# Power.net
KiCad netlist of a schematic drawn in Altium Designer
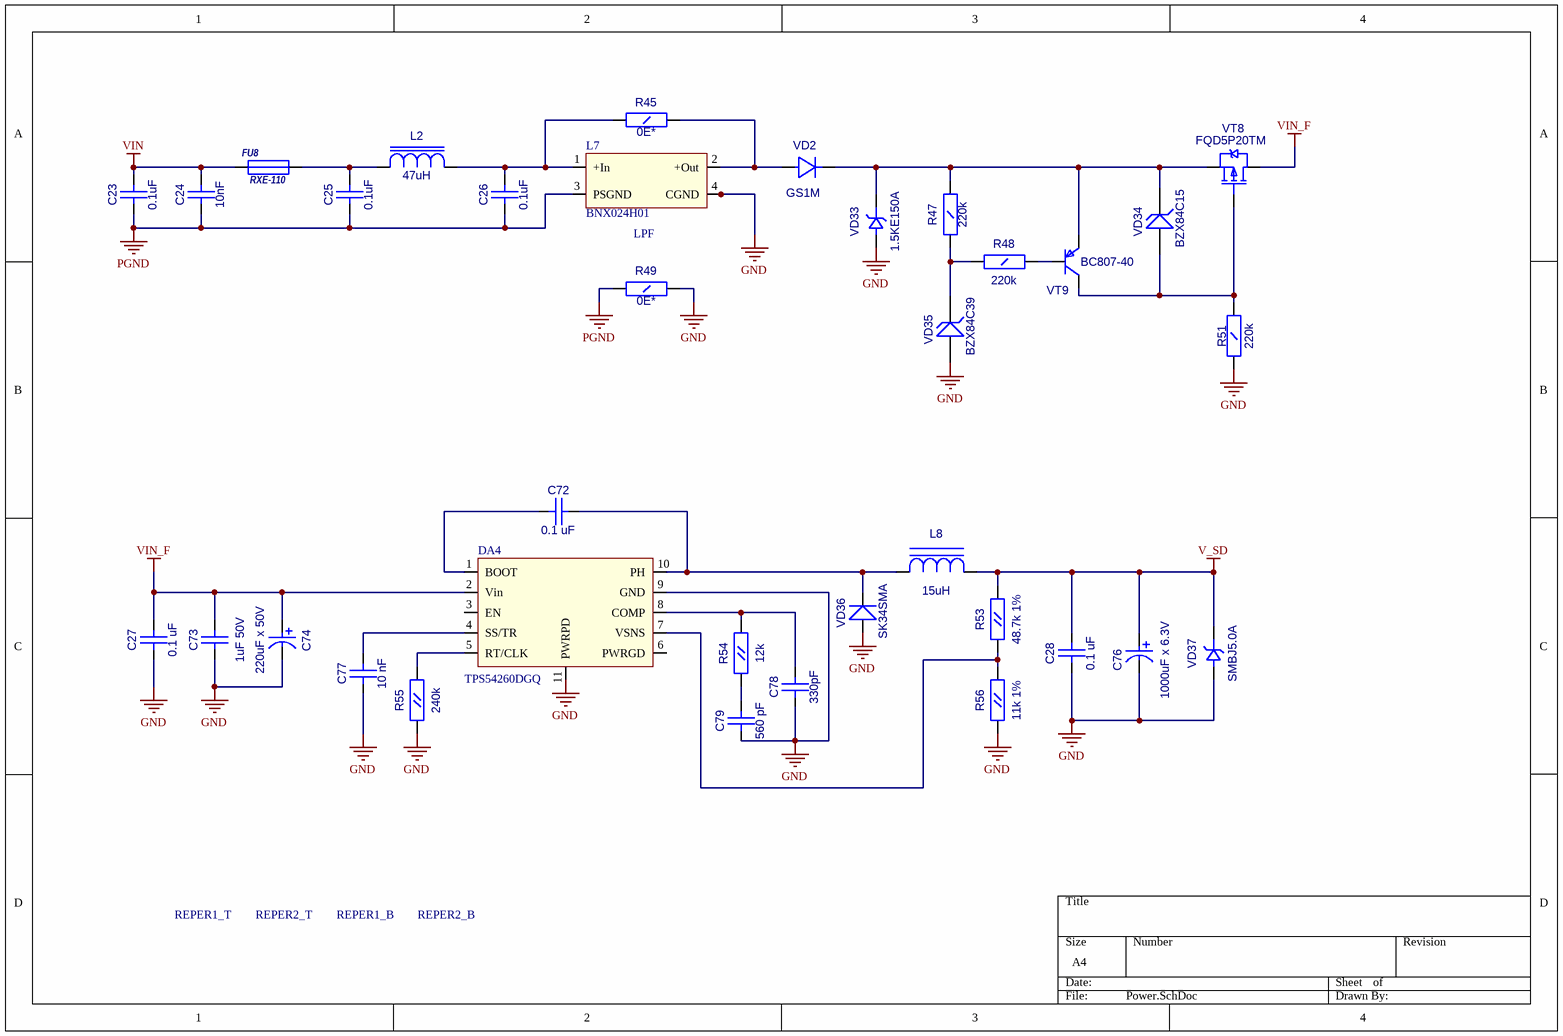
[diagram p0: Power.SchDoc]

(export (version "E")
  (design (tool "Eeschema 10.0.6"))
  (components
    (comp (ref "C23")
      (value "0.1uF")
      (footprint "CC1206")
      (description "CC1206")
      (libsource (lib "gprs_modem_2") (part "CC1206"))
    )
    (comp (ref "C24")
      (value "10nF")
      (footprint "CC1206")
      (description "CC1206")
      (libsource (lib "gprs_modem_2") (part "CC1206"))
    )
    (comp (ref "C25")
      (value "0.1uF")
      (footprint "CC1206")
      (description "CC1206")
      (libsource (lib "gprs_modem_2") (part "CC1206"))
    )
    (comp (ref "C26")
      (value "0.1uF")
      (footprint "CC1206")
      (description "CC1206")
      (libsource (lib "gprs_modem_2") (part "CC1206"))
    )
    (comp (ref "C27")
      (value "0.1 uF")
      (footprint "CC0603")
      (description "CC0603")
      (libsource (lib "gprs_modem_2") (part "CC0603"))
    )
    (comp (ref "C28")
      (value "0.1 uF")
      (footprint "CC0603")
      (description "CC0603")
      (libsource (lib "*") (part "CC0603"))
    )
    (comp (ref "C72")
      (value "0.1 uF")
      (footprint "CC0603")
      (description "CC0603")
      (libsource (lib "gprs_modem_2") (part "CC0603"))
    )
    (comp (ref "C73")
      (value "1uF 50V")
      (footprint "CC1206")
      (description "CC1206")
      (libsource (lib "gprs_modem_2") (part "CC1206"))
    )
    (comp (ref "C74")
      (value "220uF x 50V")
      (footprint "CC16X10_CAP0.5(1)(Primary)")
      (description "CAP0.5(1)")
      (libsource (lib "gprs_modem") (part "CAP0.5(1)"))
    )
    (comp (ref "C76")
      (value "1000uF x 6.3V")
      (footprint "CC16X10_CAP0.5(1)(Primary)")
      (description "CAP0.5(1)")
      (libsource (lib "gprs_modem") (part "CAP0.5(1)"))
    )
    (comp (ref "C77")
      (value "10 nF")
      (footprint "CC0603")
      (description "CC0603")
      (libsource (lib "gprs_modem_2") (part "CC0603"))
    )
    (comp (ref "C78")
      (value "330pF")
      (footprint "CC0603")
      (description "CC0603")
      (libsource (lib "gprs_modem_2") (part "CC0603"))
    )
    (comp (ref "C79")
      (value "560 pF")
      (footprint "CC0603")
      (description "CC0603")
      (libsource (lib "gprs_modem_2") (part "CC0603"))
    )
    (comp (ref "DA4")
      (value "TPS54260DGQ")
      (footprint "S-PDSO-G10")
      (libsource (lib "gprs_modem") (part "TPS54260DGQ"))
    )
    (comp (ref "FU8") (value "RXE-110") (footprint "RXE-110") (libsource (lib "gprs_modem") (part "RXE-110")))
    (comp (ref "L2")
      (value "47uH")
      (footprint "SDR0603")
      (description "SDR0603")
      (libsource (lib "gprs_modem_2") (part "SDR0603"))
    )
    (comp (ref "L7")
      (value "BNX024H01")
      (footprint "BNX024")
      (description "LC Filter")
      (libsource (lib "gprs_modem") (part "BNX024H01"))
    )
    (comp (ref "L8")
      (value "15uH")
      (footprint "SDR0805")
      (description "SDR0805")
      (libsource (lib "gprs_modem") (part "SDR0805"))
    )
    (comp (ref "R45")
      (value "0E*")
      (footprint "RC1206")
      (description "RC1206")
      (libsource (lib "gprs_modem_2") (part "RC1206"))
    )
    (comp (ref "R47")
      (value "220k")
      (footprint "RC1206")
      (description "RC1206")
      (libsource (lib "gprs_modem_2") (part "RC1206"))
    )
    (comp (ref "R48")
      (value "220k")
      (footprint "RC1206")
      (description "RC1206")
      (libsource (lib "gprs_modem_2") (part "RC1206"))
    )
    (comp (ref "R49")
      (value "0E*")
      (footprint "RC1206")
      (description "RC1206")
      (libsource (lib "gprs_modem_2") (part "RC1206"))
    )
    (comp (ref "R51")
      (value "220k")
      (footprint "RC1206")
      (description "RC1206")
      (libsource (lib "gprs_modem_2") (part "RC1206"))
    )
    (comp (ref "R53")
      (value "48.7k 1%")
      (footprint "RC0603")
      (description "RC0603")
      (libsource (lib "gprs_modem_2") (part "RC0603"))
    )
    (comp (ref "R54")
      (value "12k")
      (footprint "RC0603")
      (description "RC0603")
      (libsource (lib "gprs_modem_2") (part "RC0603"))
    )
    (comp (ref "R55")
      (value "240k")
      (footprint "RC0603")
      (description "RC0603")
      (libsource (lib "gprs_modem_2") (part "RC0603"))
    )
    (comp (ref "R56")
      (value "11k 1%")
      (footprint "RC0603")
      (description "RC0603")
      (libsource (lib "gprs_modem_2") (part "RC0603"))
    )
    (comp (ref "REPER1_B")
      (value "REPER1.2")
      (footprint "REPER1.2")
      (libsource (lib "gprs_modem") (part "REPER1.2"))
    )
    (comp (ref "REPER1_T")
      (value "REPER1.2")
      (footprint "REPER1.2")
      (libsource (lib "gprs_modem") (part "REPER1.2"))
    )
    (comp (ref "REPER2_B")
      (value "REPER1.2")
      (footprint "REPER1.2")
      (libsource (lib "gprs_modem") (part "REPER1.2"))
    )
    (comp (ref "REPER2_T")
      (value "REPER1.2")
      (footprint "REPER1.2")
      (libsource (lib "gprs_modem") (part "REPER1.2"))
    )
    (comp (ref "VD2") (value "GS1M") (footprint "SMA") (libsource (lib "gprs_modem") (part "GS1M")))
    (comp (ref "VD33")
      (value "1.5KE150A")
      (footprint "DO-201")
      (description "1.5KE")
      (libsource (lib "gprs_modem") (part "1.5KE"))
    )
    (comp (ref "VD34")
      (value "BZX84C15")
      (footprint "SOT-23(123)")
      (description "Zener Voltage Regulator Diode")
      (libsource (lib "gprs_modem_2") (part "BZX84"))
    )
    (comp (ref "VD35")
      (value "BZX84C39")
      (footprint "SOT-23(123)")
      (description "Zener Voltage Regulator Diode")
      (libsource (lib "gprs_modem_2") (part "BZX84"))
    )
    (comp (ref "VD36")
      (value "SK34SMA")
      (footprint "SMA")
      (description "Schottky Rectifier")
      (libsource (lib "gprs_modem") (part "SK34SMA"))
    )
    (comp (ref "VD37")
      (value "SMBJ5.0A")
      (footprint "SMB")
      (description "SMBJ")
      (libsource (lib "gprs_modem") (part "SMBJ"))
    )
    (comp (ref "VT8")
      (value "FQD5P20TM")
      (footprint "D-PAK(TO-252AA)")
      (description "HEXFET Power MOSFET")
      (libsource (lib "gprs_modem") (part "IRFR9220"))
    )
    (comp (ref "VT9")
      (value "BC807-40")
      (footprint "SOT-23(123)")
      (description "BC857B")
      (libsource (lib "gprs_modem") (part "BC857B"))
    )
  )
  (nets
    (net (code "1") (name "GND") (class "Default")
      (node (ref "C27") (pin "1") (pinfunction "A_1") (pintype "passive"))
      (node (ref "C28") (pin "2") (pinfunction "B_2") (pintype "passive"))
      (node (ref "C73") (pin "1") (pinfunction "A_1") (pintype "passive"))
      (node (ref "C74") (pin "1") (pintype "passive"))
      (node (ref "C76") (pin "1") (pintype "passive"))
      (node (ref "C77") (pin "1") (pinfunction "A_1") (pintype "passive"))
      (node (ref "C78") (pin "1") (pinfunction "A_1") (pintype "passive"))
      (node (ref "C79") (pin "1") (pinfunction "A_1") (pintype "passive"))
      (node (ref "DA4") (pin "11") (pinfunction "PWRPD_11") (pintype "passive"))
      (node (ref "DA4") (pin "9") (pinfunction "GND_9") (pintype "passive"))
      (node (ref "L7") (pin "4") (pinfunction "CGND_4") (pintype "passive"))
      (node (ref "L7") (pin "5") (pinfunction "5_5") (pintype "passive"))
      (node (ref "L7") (pin "6") (pinfunction "6_6") (pintype "passive"))
      (node (ref "R49") (pin "2") (pinfunction "B_2") (pintype "passive"))
      (node (ref "R51") (pin "2") (pinfunction "B_2") (pintype "passive"))
      (node (ref "R55") (pin "1") (pinfunction "A_1") (pintype "passive"))
      (node (ref "R56") (pin "1") (pinfunction "A_1") (pintype "passive"))
      (node (ref "VD33") (pin "1") (pinfunction "A_1") (pintype "passive"))
      (node (ref "VD35") (pin "1") (pinfunction "A_1") (pintype "passive"))
      (node (ref "VD36") (pin "1") (pinfunction "A_1") (pintype "passive"))
      (node (ref "VD37") (pin "1") (pinfunction "A_1") (pintype "passive"))
    )
    (net (code "2") (name "Net-(C25-B)") (class "Default")
      (node (ref "C25") (pin "2") (pinfunction "B_2") (pintype "passive"))
      (node (ref "FU8") (pin "2") (pintype "passive"))
      (node (ref "L2") (pin "1") (pintype "passive"))
    )
    (net (code "3") (name "Net-(C26-B)") (class "Default")
      (node (ref "C26") (pin "2") (pinfunction "B_2") (pintype "passive"))
      (node (ref "L2") (pin "2") (pintype "passive"))
      (node (ref "L7") (pin "1") (pinfunction "+In_1") (pintype "passive"))
      (node (ref "R45") (pin "1") (pinfunction "A_1") (pintype "passive"))
    )
    (net (code "4") (name "Net-(C72-A)") (class "Default")
      (node (ref "C72") (pin "1") (pinfunction "A_1") (pintype "passive"))
      (node (ref "DA4") (pin "1") (pinfunction "BOOT_1") (pintype "passive"))
    )
    (net (code "5") (name "Net-(C72-B)") (class "Default")
      (node (ref "C72") (pin "2") (pinfunction "B_2") (pintype "passive"))
      (node (ref "DA4") (pin "10") (pinfunction "PH_10") (pintype "passive"))
      (node (ref "L8") (pin "1") (pinfunction "C_1") (pintype "passive"))
      (node (ref "VD36") (pin "2") (pinfunction "K_2") (pintype "passive"))
    )
    (net (code "6") (name "Net-(C77-B)") (class "Default")
      (node (ref "C77") (pin "2") (pinfunction "B_2") (pintype "passive"))
      (node (ref "DA4") (pin "4") (pinfunction "SS/TR_4") (pintype "passive"))
    )
    (net (code "7") (name "Net-(C78-B)") (class "Default")
      (node (ref "C78") (pin "2") (pinfunction "B_2") (pintype "passive"))
      (node (ref "DA4") (pin "8") (pinfunction "COMP_8") (pintype "passive"))
      (node (ref "R54") (pin "2") (pinfunction "B_2") (pintype "passive"))
    )
    (net (code "8") (name "Net-(C79-B)") (class "Default")
      (node (ref "C79") (pin "2") (pinfunction "B_2") (pintype "passive"))
      (node (ref "R54") (pin "1") (pinfunction "A_1") (pintype "passive"))
    )
    (net (code "9") (name "Net-(DA4-RT{slash}CLK)") (class "Default")
      (node (ref "DA4") (pin "5") (pinfunction "RT/CLK_5") (pintype "passive"))
      (node (ref "R55") (pin "2") (pinfunction "B_2") (pintype "passive"))
    )
    (net (code "10") (name "Net-(DA4-VSNS)") (class "Default")
      (node (ref "DA4") (pin "7") (pinfunction "VSNS_7") (pintype "passive"))
      (node (ref "R53") (pin "1") (pinfunction "A_1") (pintype "passive"))
      (node (ref "R56") (pin "2") (pinfunction "B_2") (pintype "passive"))
    )
    (net (code "11") (name "Net-(L7-+Out)") (class "Default")
      (node (ref "L7") (pin "2") (pinfunction "+Out_2") (pintype "passive"))
      (node (ref "R45") (pin "2") (pinfunction "B_2") (pintype "passive"))
      (node (ref "VD2") (pin "1") (pinfunction "A_1") (pintype "passive"))
    )
    (net (code "12") (name "Net-(R47-A)") (class "Default")
      (node (ref "R47") (pin "1") (pinfunction "A_1") (pintype "passive"))
      (node (ref "R48") (pin "1") (pinfunction "A_1") (pintype "passive"))
      (node (ref "VD35") (pin "3") (pinfunction "K_3") (pintype "passive"))
    )
    (net (code "13") (name "Net-(R47-B)") (class "Default")
      (node (ref "R47") (pin "2") (pinfunction "B_2") (pintype "passive"))
      (node (ref "VD2") (pin "2") (pinfunction "K_2") (pintype "passive"))
      (node (ref "VD33") (pin "2") (pinfunction "K_2") (pintype "passive"))
      (node (ref "VD34") (pin "3") (pinfunction "K_3") (pintype "passive"))
      (node (ref "VT8") (pin "2") (pinfunction "S_2") (pintype "passive"))
      (node (ref "VT9") (pin "2") (pinfunction "E_2") (pintype "passive"))
    )
    (net (code "14") (name "Net-(R48-B)") (class "Default")
      (node (ref "R48") (pin "2") (pinfunction "B_2") (pintype "passive"))
      (node (ref "VT9") (pin "1") (pinfunction "B_1") (pintype "passive"))
    )
    (net (code "15") (name "Net-(R51-A)") (class "Default")
      (node (ref "R51") (pin "1") (pinfunction "A_1") (pintype "passive"))
      (node (ref "VD34") (pin "1") (pinfunction "A_1") (pintype "passive"))
      (node (ref "VT8") (pin "1") (pinfunction "G_1") (pintype "passive"))
      (node (ref "VT9") (pin "3") (pinfunction "C_3") (pintype "passive"))
    )
    (net (code "16") (name "PGND") (class "Default")
      (node (ref "C23") (pin "1") (pinfunction "A_1") (pintype "passive"))
      (node (ref "C24") (pin "1") (pinfunction "A_1") (pintype "passive"))
      (node (ref "C25") (pin "1") (pinfunction "A_1") (pintype "passive"))
      (node (ref "C26") (pin "1") (pinfunction "A_1") (pintype "passive"))
      (node (ref "L7") (pin "3") (pinfunction "PSGND_3") (pintype "passive"))
      (node (ref "R49") (pin "1") (pinfunction "A_1") (pintype "passive"))
    )
    (net (code "17") (name "VIN") (class "Default")
      (node (ref "C23") (pin "2") (pinfunction "B_2") (pintype "passive"))
      (node (ref "C24") (pin "2") (pinfunction "B_2") (pintype "passive"))
      (node (ref "FU8") (pin "1") (pintype "passive"))
    )
    (net (code "18") (name "VIN_F") (class "Default")
      (node (ref "C27") (pin "2") (pinfunction "B_2") (pintype "passive"))
      (node (ref "C73") (pin "2") (pinfunction "B_2") (pintype "passive"))
      (node (ref "C74") (pin "2") (pintype "passive"))
      (node (ref "DA4") (pin "2") (pinfunction "Vin_2") (pintype "passive"))
      (node (ref "VT8") (pin "3") (pinfunction "D_3") (pintype "passive"))
    )
    (net (code "19") (name "V_SD") (class "Default")
      (node (ref "C28") (pin "1") (pinfunction "A_1") (pintype "passive"))
      (node (ref "C76") (pin "2") (pintype "passive"))
      (node (ref "L8") (pin "2") (pinfunction "A_2") (pintype "passive"))
      (node (ref "R53") (pin "2") (pinfunction "B_2") (pintype "passive"))
      (node (ref "VD37") (pin "2") (pinfunction "K_2") (pintype "passive"))
    )
    (net (code "20") (name "unconnected-(DA4-EN-Pad3)") (class "Default")
      (node (ref "DA4") (pin "3") (pinfunction "EN_3") (pintype "passive"))
    )
    (net (code "21") (name "unconnected-(DA4-PWRGD-Pad6)") (class "Default")
      (node (ref "DA4") (pin "6") (pinfunction "PWRGD_6") (pintype "passive"))
    )
    (net (code "22") (name "unconnected-(REPER1_B-Pad1)") (class "Default")
      (node (ref "REPER1_B") (pin "1") (pintype "passive"))
    )
    (net (code "23") (name "unconnected-(REPER1_T-Pad1)") (class "Default")
      (node (ref "REPER1_T") (pin "1") (pintype "passive"))
    )
    (net (code "24") (name "unconnected-(REPER2_B-Pad1)") (class "Default")
      (node (ref "REPER2_B") (pin "1") (pintype "passive"))
    )
    (net (code "25") (name "unconnected-(REPER2_T-Pad1)") (class "Default")
      (node (ref "REPER2_T") (pin "1") (pintype "passive"))
    )
  )
)
